# PCB_LED_CALENDAR__AMBIENT_LIGHT_SENS.net
KiCad netlist of a schematic drawn in Altium Designer
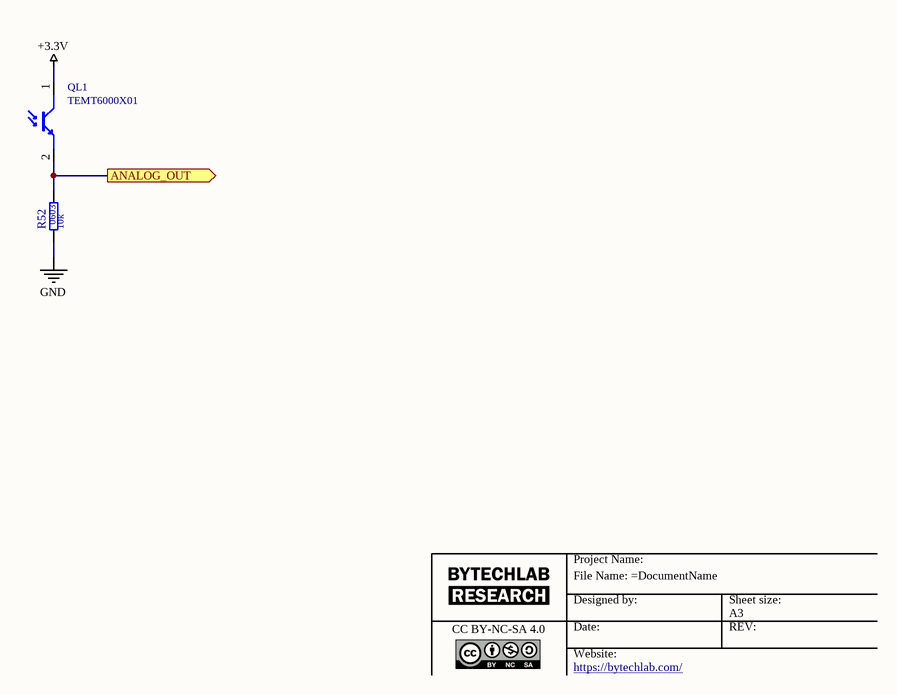
[diagram p0: PCB_LED_CALENDAR__AMBIENT_LIGHT_SENS.SchDoc]

(export (version "E")
  (design (tool "Eeschema 10.0.6"))
  (components
    (comp (ref "QL1")
      (value "TEMT6000X01")
      (footprint "TEMT6000X01")
      (description "1206 Ambient Light Sensors ROHS")
      (fields (field (name "MANUFACTURER") "Vishay Intertech"))
      (libsource (lib "PCB_LED_CALENDAR") (part "QL_TEMT6000X01"))
    )
    (comp (ref "R52")
      (value "10k")
      (footprint "R_0603_1608")
      (fields
        (field (name "SCH_FOOTPRINT") "0603")
        (field (name "PART NUMBER") "R_10k_0603_1")
        (field (name "VOLTAGE") "75V")
        (field (name "POWER") "100mW")
      )
      (libsource (lib "Library") (part "R"))
    )
  )
  (nets
    (net (code "1") (name "+3.3V") (class "Default") (node (ref "QL1") (pin "1") (pintype "passive")))
    (net (code "2") (name "/ANALOG_OUT") (class "Default")
      (node (ref "QL1") (pin "2") (pintype "passive"))
      (node (ref "R52") (pin "2") (pinfunction "2_2") (pintype "passive"))
    )
    (net (code "3") (name "GND") (class "Default")
      (node (ref "R52") (pin "1") (pinfunction "1_1") (pintype "passive"))
    )
  )
)
